# Sheet1.net
KiCad netlist of a schematic drawn in Altium Designer
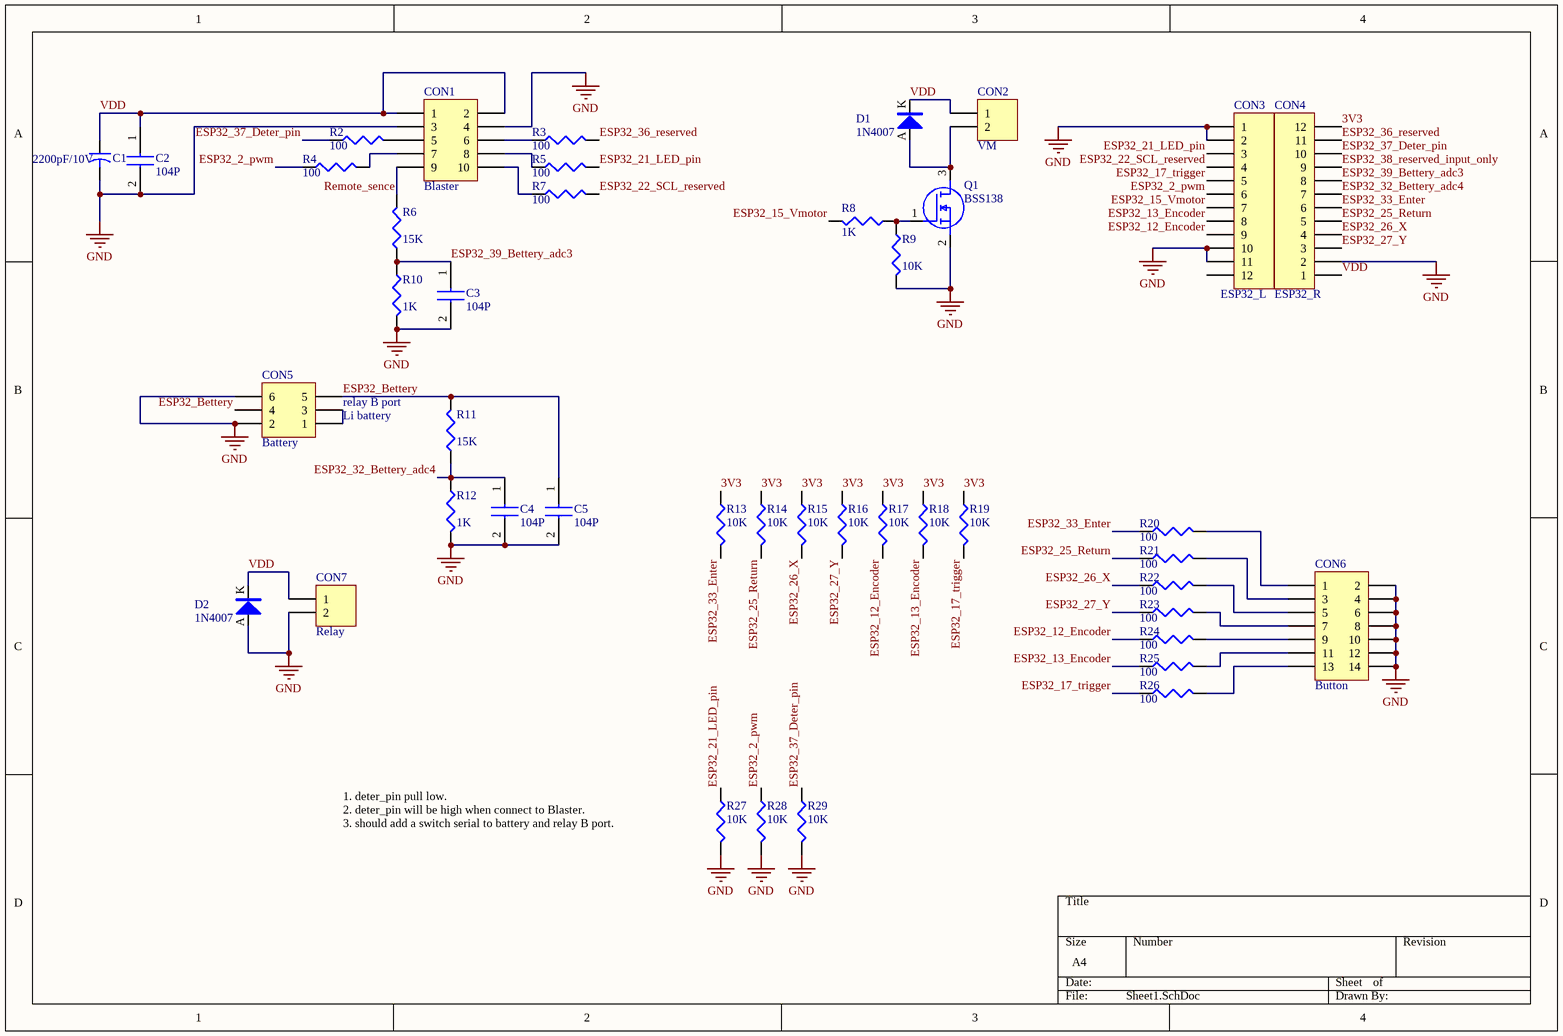
[diagram p0: Sheet1.SchDoc]

(export (version "E")
  (design (tool "Eeschema 10.0.6"))
  (components
    (comp (ref "C1")
      (value "2200pF/10V")
      (footprint "CAPR5-4X5")
      (description "Capacitor")
      (fields (field (name "Comment") "Cap2") (field (name "PUBLISHER") "Altium Limited"))
      (libsource (lib "Miscellaneous Devices") (part "Cap2"))
    )
    (comp (ref "C2")
      (value "104P")
      (footprint "SamacSys:CAPC1608X90N")
      (description "Capacitor")
      (fields
        (field (name "MANUFACTURER_PART_NUMBER") "CC0603KRX7R7BB103")
        (field (name "MOUSER PART NUMBER") "603-CC603KRX7R7BB103")
      )
      (libsource (lib "*") (part "CC0603KRX7R7BB103"))
    )
    (comp (ref "C3")
      (value "104P")
      (footprint "SamacSys:CAPC1608X90N")
      (description "Capacitor")
      (fields
        (field (name "MANUFACTURER_PART_NUMBER") "CC0603KRX7R7BB103")
        (field (name "MOUSER PART NUMBER") "603-CC603KRX7R7BB103")
      )
      (libsource (lib "*") (part "CC0603KRX7R7BB103"))
    )
    (comp (ref "C4")
      (value "104P")
      (footprint "SamacSys:CAPC1608X90N")
      (description "Capacitor")
      (fields
        (field (name "MANUFACTURER_PART_NUMBER") "CC0603KRX7R7BB103")
        (field (name "MOUSER PART NUMBER") "603-CC603KRX7R7BB103")
      )
      (libsource (lib "*") (part "CC0603KRX7R7BB103"))
    )
    (comp (ref "C5")
      (value "104P")
      (footprint "SamacSys:CAPC1608X90N")
      (description "Capacitor")
      (fields
        (field (name "MANUFACTURER_PART_NUMBER") "CC0603KRX7R7BB103")
        (field (name "MOUSER PART NUMBER") "603-CC603KRX7R7BB103")
      )
      (libsource (lib "*") (part "CC0603KRX7R7BB103"))
    )
    (comp (ref "CON1")
      (value "Blaster")
      (footprint "HDR2X5")
      (description "Header, 5-Pin, Dual row")
      (fields (field (name "PUBLISHER") "Altium Limited"))
      (libsource (lib "Miscellaneous Connectors") (part "Header 5X2"))
    )
    (comp (ref "CON2")
      (value "VM")
      (footprint "HDR1X2")
      (description "Header, 2-Pin")
      (fields (field (name "PUBLISHER") "Altium Limited"))
      (libsource (lib "Miscellaneous Connectors") (part "Header 2"))
    )
    (comp (ref "CON3")
      (value "ESP32_L")
      (footprint "HDR1X12")
      (description "Header, 12-Pin")
      (fields (field (name "PUBLISHER") "Altium Limited"))
      (libsource (lib "") (part "Header 12_1"))
    )
    (comp (ref "CON4")
      (value "ESP32_R")
      (footprint "HDR1X12")
      (description "Header, 12-Pin")
      (fields (field (name "PUBLISHER") "Altium Limited"))
      (libsource (lib "Miscellaneous Connectors") (part "Header 12"))
    )
    (comp (ref "CON5")
      (value "Battery")
      (footprint "HDR2X3")
      (description "Header, 3-Pin, Dual row")
      (fields (field (name "PUBLISHER") "Altium Limited"))
      (libsource (lib "Miscellaneous Connectors") (part "Header 3X2"))
    )
    (comp (ref "CON6")
      (value "Button")
      (footprint "HDR2X7")
      (description "Header, 7-Pin, Dual row")
      (fields (field (name "PUBLISHER") "Altium Limited"))
      (libsource (lib "Miscellaneous Connectors") (part "Header 7X2"))
    )
    (comp (ref "CON7")
      (value "Relay")
      (footprint "HDR1X2")
      (description "Header, 2-Pin")
      (fields (field (name "PUBLISHER") "Altium Limited"))
      (libsource (lib "Miscellaneous Connectors") (part "Header 2"))
    )
    (comp (ref "D1") (value "1N4007") (footprint "D3216") (libsource (lib "Diode") (part "SMD-D")))
    (comp (ref "D2") (value "1N4007") (footprint "D3216") (libsource (lib "Diode") (part "SMD-D")))
    (comp (ref "Q1")
      (value "BSS138")
      (footprint "SamacSys:SOT95P240X120-3N")
      (description "MOSFET (N-Channel)")
      (fields (field (name "MOUSER PART NUMBER") "512-BSS138"))
      (libsource (lib "*") (part "BSS138"))
    )
    (comp (ref "R2")
      (value "100")
      (footprint "J1-0603")
      (description "Resistor")
      (fields (field (name "Comment") "Res3") (field (name "PUBLISHER") "Altium Limited"))
      (libsource (lib "Miscellaneous Devices") (part "Res3"))
    )
    (comp (ref "R3")
      (value "100")
      (footprint "J1-0603")
      (description "Resistor")
      (fields (field (name "Comment") "Res3") (field (name "PUBLISHER") "Altium Limited"))
      (libsource (lib "Miscellaneous Devices") (part "Res3"))
    )
    (comp (ref "R4")
      (value "100")
      (footprint "J1-0603")
      (description "Resistor")
      (fields (field (name "Comment") "Res3") (field (name "PUBLISHER") "Altium Limited"))
      (libsource (lib "Miscellaneous Devices") (part "Res3"))
    )
    (comp (ref "R5")
      (value "100")
      (footprint "J1-0603")
      (description "Resistor")
      (fields (field (name "Comment") "Res3") (field (name "PUBLISHER") "Altium Limited"))
      (libsource (lib "Miscellaneous Devices") (part "Res3"))
    )
    (comp (ref "R6")
      (value "15K")
      (footprint "J1-0603")
      (description "Resistor")
      (fields (field (name "Comment") "Res3") (field (name "PUBLISHER") "Altium Limited"))
      (libsource (lib "Miscellaneous Devices") (part "Res3"))
    )
    (comp (ref "R7")
      (value "100")
      (footprint "J1-0603")
      (description "Resistor")
      (fields (field (name "Comment") "Res3") (field (name "PUBLISHER") "Altium Limited"))
      (libsource (lib "Miscellaneous Devices") (part "Res3"))
    )
    (comp (ref "R8")
      (value "1K")
      (footprint "J1-0603")
      (description "Resistor")
      (fields (field (name "Comment") "Res3") (field (name "PUBLISHER") "Altium Limited"))
      (libsource (lib "Miscellaneous Devices") (part "Res3"))
    )
    (comp (ref "R9")
      (value "10K")
      (footprint "J1-0603")
      (description "Resistor")
      (fields (field (name "Comment") "Res3") (field (name "PUBLISHER") "Altium Limited"))
      (libsource (lib "Miscellaneous Devices") (part "Res3"))
    )
    (comp (ref "R10")
      (value "1K")
      (footprint "J1-0603")
      (description "Resistor")
      (fields (field (name "Comment") "Res3") (field (name "PUBLISHER") "Altium Limited"))
      (libsource (lib "Miscellaneous Devices") (part "Res3"))
    )
    (comp (ref "R11")
      (value "15K")
      (footprint "J1-0603")
      (description "Resistor")
      (fields (field (name "Comment") "Res3") (field (name "PUBLISHER") "Altium Limited"))
      (libsource (lib "Miscellaneous Devices") (part "Res3"))
    )
    (comp (ref "R12")
      (value "1K")
      (footprint "J1-0603")
      (description "Resistor")
      (fields (field (name "Comment") "Res3") (field (name "PUBLISHER") "Altium Limited"))
      (libsource (lib "Miscellaneous Devices") (part "Res3"))
    )
    (comp (ref "R13")
      (value "10K")
      (footprint "J1-0603")
      (description "Resistor")
      (fields (field (name "Comment") "Res3") (field (name "PUBLISHER") "Altium Limited"))
      (libsource (lib "Miscellaneous Devices") (part "Res3"))
    )
    (comp (ref "R14")
      (value "10K")
      (footprint "J1-0603")
      (description "Resistor")
      (fields (field (name "Comment") "Res3") (field (name "PUBLISHER") "Altium Limited"))
      (libsource (lib "Miscellaneous Devices") (part "Res3"))
    )
    (comp (ref "R15")
      (value "10K")
      (footprint "J1-0603")
      (description "Resistor")
      (fields (field (name "Comment") "Res3") (field (name "PUBLISHER") "Altium Limited"))
      (libsource (lib "Miscellaneous Devices") (part "Res3"))
    )
    (comp (ref "R16")
      (value "10K")
      (footprint "J1-0603")
      (description "Resistor")
      (fields (field (name "Comment") "Res3") (field (name "PUBLISHER") "Altium Limited"))
      (libsource (lib "Miscellaneous Devices") (part "Res3"))
    )
    (comp (ref "R17")
      (value "10K")
      (footprint "J1-0603")
      (description "Resistor")
      (fields (field (name "Comment") "Res3") (field (name "PUBLISHER") "Altium Limited"))
      (libsource (lib "Miscellaneous Devices") (part "Res3"))
    )
    (comp (ref "R18")
      (value "10K")
      (footprint "J1-0603")
      (description "Resistor")
      (fields (field (name "Comment") "Res3") (field (name "PUBLISHER") "Altium Limited"))
      (libsource (lib "Miscellaneous Devices") (part "Res3"))
    )
    (comp (ref "R19")
      (value "10K")
      (footprint "J1-0603")
      (description "Resistor")
      (fields (field (name "Comment") "Res3") (field (name "PUBLISHER") "Altium Limited"))
      (libsource (lib "Miscellaneous Devices") (part "Res3"))
    )
    (comp (ref "R20")
      (value "100")
      (footprint "J1-0603")
      (description "Resistor")
      (fields (field (name "Comment") "Res3") (field (name "PUBLISHER") "Altium Limited"))
      (libsource (lib "Miscellaneous Devices") (part "Res3"))
    )
    (comp (ref "R21")
      (value "100")
      (footprint "J1-0603")
      (description "Resistor")
      (fields (field (name "Comment") "Res3") (field (name "PUBLISHER") "Altium Limited"))
      (libsource (lib "Miscellaneous Devices") (part "Res3"))
    )
    (comp (ref "R22")
      (value "100")
      (footprint "J1-0603")
      (description "Resistor")
      (fields (field (name "Comment") "Res3") (field (name "PUBLISHER") "Altium Limited"))
      (libsource (lib "Miscellaneous Devices") (part "Res3"))
    )
    (comp (ref "R23")
      (value "100")
      (footprint "J1-0603")
      (description "Resistor")
      (fields (field (name "Comment") "Res3") (field (name "PUBLISHER") "Altium Limited"))
      (libsource (lib "Miscellaneous Devices") (part "Res3"))
    )
    (comp (ref "R24")
      (value "100")
      (footprint "J1-0603")
      (description "Resistor")
      (fields (field (name "Comment") "Res3") (field (name "PUBLISHER") "Altium Limited"))
      (libsource (lib "Miscellaneous Devices") (part "Res3"))
    )
    (comp (ref "R25")
      (value "100")
      (footprint "J1-0603")
      (description "Resistor")
      (fields (field (name "Comment") "Res3") (field (name "PUBLISHER") "Altium Limited"))
      (libsource (lib "Miscellaneous Devices") (part "Res3"))
    )
    (comp (ref "R26")
      (value "100")
      (footprint "J1-0603")
      (description "Resistor")
      (fields (field (name "Comment") "Res3") (field (name "PUBLISHER") "Altium Limited"))
      (libsource (lib "Miscellaneous Devices") (part "Res3"))
    )
    (comp (ref "R27")
      (value "10K")
      (footprint "J1-0603")
      (description "Resistor")
      (fields (field (name "Comment") "Res3") (field (name "PUBLISHER") "Altium Limited"))
      (libsource (lib "Miscellaneous Devices") (part "Res3"))
    )
    (comp (ref "R28")
      (value "10K")
      (footprint "J1-0603")
      (description "Resistor")
      (fields (field (name "Comment") "Res3") (field (name "PUBLISHER") "Altium Limited"))
      (libsource (lib "Miscellaneous Devices") (part "Res3"))
    )
    (comp (ref "R29")
      (value "10K")
      (footprint "J1-0603")
      (description "Resistor")
      (fields (field (name "Comment") "Res3") (field (name "PUBLISHER") "Altium Limited"))
      (libsource (lib "Miscellaneous Devices") (part "Res3"))
    )
  )
  (nets
    (net (code "1") (name "/3V3") (class "Default")
      (node (ref "CON4") (pin "12") (pinfunction "12_12") (pintype "passive"))
      (node (ref "R13") (pin "1") (pinfunction "1_1") (pintype "passive"))
      (node (ref "R14") (pin "1") (pinfunction "1_1") (pintype "passive"))
      (node (ref "R15") (pin "1") (pinfunction "1_1") (pintype "passive"))
      (node (ref "R16") (pin "1") (pinfunction "1_1") (pintype "passive"))
      (node (ref "R17") (pin "1") (pinfunction "1_1") (pintype "passive"))
      (node (ref "R18") (pin "1") (pinfunction "1_1") (pintype "passive"))
      (node (ref "R19") (pin "1") (pinfunction "1_1") (pintype "passive"))
    )
    (net (code "2") (name "/ESP32_2_pwm") (class "Default")
      (node (ref "CON3") (pin "6") (pinfunction "6_6") (pintype "passive"))
      (node (ref "R28") (pin "1") (pinfunction "1_1") (pintype "passive"))
      (node (ref "R4") (pin "1") (pinfunction "1_1") (pintype "passive"))
    )
    (net (code "3") (name "/ESP32_12_Encoder") (class "Default")
      (node (ref "CON3") (pin "9") (pinfunction "9_9") (pintype "passive"))
      (node (ref "R17") (pin "2") (pinfunction "2_2") (pintype "passive"))
      (node (ref "R24") (pin "1") (pinfunction "1_1") (pintype "passive"))
    )
    (net (code "4") (name "/ESP32_13_Encoder") (class "Default")
      (node (ref "CON3") (pin "8") (pinfunction "8_8") (pintype "passive"))
      (node (ref "R18") (pin "2") (pinfunction "2_2") (pintype "passive"))
      (node (ref "R25") (pin "1") (pinfunction "1_1") (pintype "passive"))
    )
    (net (code "5") (name "/ESP32_15_Vmotor") (class "Default")
      (node (ref "CON3") (pin "7") (pinfunction "7_7") (pintype "passive"))
      (node (ref "R8") (pin "2") (pinfunction "2_2") (pintype "passive"))
    )
    (net (code "6") (name "/ESP32_17_trigger") (class "Default")
      (node (ref "CON3") (pin "5") (pinfunction "5_5") (pintype "passive"))
      (node (ref "R19") (pin "2") (pinfunction "2_2") (pintype "passive"))
      (node (ref "R26") (pin "1") (pinfunction "1_1") (pintype "passive"))
    )
    (net (code "7") (name "/ESP32_21_LED_pin") (class "Default")
      (node (ref "CON3") (pin "3") (pinfunction "3_3") (pintype "passive"))
      (node (ref "R27") (pin "1") (pinfunction "1_1") (pintype "passive"))
      (node (ref "R5") (pin "2") (pinfunction "2_2") (pintype "passive"))
    )
    (net (code "8") (name "/ESP32_22_SCL_reserved") (class "Default")
      (node (ref "CON3") (pin "4") (pinfunction "4_4") (pintype "passive"))
      (node (ref "R7") (pin "2") (pinfunction "2_2") (pintype "passive"))
    )
    (net (code "9") (name "/ESP32_25_Return") (class "Default")
      (node (ref "CON4") (pin "5") (pinfunction "5_5") (pintype "passive"))
      (node (ref "R14") (pin "2") (pinfunction "2_2") (pintype "passive"))
      (node (ref "R21") (pin "1") (pinfunction "1_1") (pintype "passive"))
    )
    (net (code "10") (name "/ESP32_26_X") (class "Default")
      (node (ref "CON4") (pin "4") (pinfunction "4_4") (pintype "passive"))
      (node (ref "R15") (pin "2") (pinfunction "2_2") (pintype "passive"))
      (node (ref "R22") (pin "1") (pinfunction "1_1") (pintype "passive"))
    )
    (net (code "11") (name "/ESP32_27_Y") (class "Default")
      (node (ref "CON4") (pin "3") (pinfunction "3_3") (pintype "passive"))
      (node (ref "R16") (pin "2") (pinfunction "2_2") (pintype "passive"))
      (node (ref "R23") (pin "1") (pinfunction "1_1") (pintype "passive"))
    )
    (net (code "12") (name "/ESP32_32_Bettery_adc4") (class "Default")
      (node (ref "C4") (pin "1") (pinfunction "1_1") (pintype "passive"))
      (node (ref "CON4") (pin "7") (pinfunction "7_7") (pintype "passive"))
      (node (ref "R11") (pin "1") (pinfunction "1_1") (pintype "passive"))
      (node (ref "R12") (pin "1") (pinfunction "1_1") (pintype "passive"))
    )
    (net (code "13") (name "/ESP32_33_Enter") (class "Default")
      (node (ref "CON4") (pin "6") (pinfunction "6_6") (pintype "passive"))
      (node (ref "R13") (pin "2") (pinfunction "2_2") (pintype "passive"))
      (node (ref "R20") (pin "1") (pinfunction "1_1") (pintype "passive"))
    )
    (net (code "14") (name "/ESP32_36_reserved") (class "Default")
      (node (ref "CON4") (pin "11") (pinfunction "11_11") (pintype "passive"))
      (node (ref "R3") (pin "2") (pinfunction "2_2") (pintype "passive"))
    )
    (net (code "15") (name "/ESP32_37_Deter_pin") (class "Default")
      (node (ref "CON4") (pin "10") (pinfunction "10_10") (pintype "passive"))
      (node (ref "R2") (pin "1") (pinfunction "1_1") (pintype "passive"))
      (node (ref "R29") (pin "1") (pinfunction "1_1") (pintype "passive"))
    )
    (net (code "16") (name "/ESP32_38_reserved_input_only") (class "Default")
      (node (ref "CON4") (pin "9") (pinfunction "9_9") (pintype "passive"))
    )
    (net (code "17") (name "/ESP32_39_Bettery_adc3") (class "Default")
      (node (ref "C3") (pin "1") (pinfunction "1_1") (pintype "passive"))
      (node (ref "CON4") (pin "8") (pinfunction "8_8") (pintype "passive"))
      (node (ref "R10") (pin "1") (pinfunction "1_1") (pintype "passive"))
      (node (ref "R6") (pin "1") (pinfunction "1_1") (pintype "passive"))
    )
    (net (code "18") (name "/ESP32_Bettery") (class "Default")
      (node (ref "C5") (pin "1") (pinfunction "1_1") (pintype "passive"))
      (node (ref "CON5") (pin "4") (pinfunction "4_4") (pintype "passive"))
      (node (ref "CON5") (pin "5") (pinfunction "5_5") (pintype "passive"))
      (node (ref "R11") (pin "2") (pinfunction "2_2") (pintype "passive"))
    )
    (net (code "19") (name "/Remote_sence") (class "Default")
      (node (ref "CON1") (pin "9") (pinfunction "9_9") (pintype "passive"))
      (node (ref "R6") (pin "2") (pinfunction "2_2") (pintype "passive"))
    )
    (net (code "20") (name "/VDD") (class "Default")
      (node (ref "C1") (pin "1") (pinfunction "1_1") (pintype "passive"))
      (node (ref "C2") (pin "1") (pinfunction "1_1") (pintype "passive"))
      (node (ref "CON1") (pin "1") (pinfunction "1_1") (pintype "passive"))
      (node (ref "CON1") (pin "2") (pinfunction "2_2") (pintype "passive"))
      (node (ref "CON2") (pin "1") (pinfunction "1_1") (pintype "passive"))
      (node (ref "CON4") (pin "1") (pinfunction "1_1") (pintype "passive"))
      (node (ref "CON7") (pin "1") (pinfunction "1_1") (pintype "passive"))
      (node (ref "D1") (pin "K") (pinfunction "K_K") (pintype "passive"))
      (node (ref "D2") (pin "K") (pinfunction "K_K") (pintype "passive"))
    )
    (net (code "21") (name "GND") (class "Default")
      (node (ref "C1") (pin "2") (pinfunction "2_2") (pintype "passive"))
      (node (ref "C2") (pin "2") (pinfunction "2_2") (pintype "passive"))
      (node (ref "C3") (pin "2") (pinfunction "2_2") (pintype "passive"))
      (node (ref "C4") (pin "2") (pinfunction "2_2") (pintype "passive"))
      (node (ref "C5") (pin "2") (pinfunction "2_2") (pintype "passive"))
      (node (ref "CON1") (pin "3") (pinfunction "3_3") (pintype "passive"))
      (node (ref "CON1") (pin "4") (pinfunction "4_4") (pintype "passive"))
      (node (ref "CON3") (pin "1") (pinfunction "1_1") (pintype "passive"))
      (node (ref "CON3") (pin "10") (pinfunction "10_10") (pintype "passive"))
      (node (ref "CON3") (pin "11") (pinfunction "11_11") (pintype "passive"))
      (node (ref "CON3") (pin "2") (pinfunction "2_2") (pintype "passive"))
      (node (ref "CON4") (pin "2") (pinfunction "2_2") (pintype "passive"))
      (node (ref "CON5") (pin "2") (pinfunction "2_2") (pintype "passive"))
      (node (ref "CON5") (pin "6") (pinfunction "6_6") (pintype "passive"))
      (node (ref "CON6") (pin "10") (pinfunction "10_10") (pintype "passive"))
      (node (ref "CON6") (pin "12") (pinfunction "12_12") (pintype "passive"))
      (node (ref "CON6") (pin "14") (pinfunction "14_14") (pintype "passive"))
      (node (ref "CON6") (pin "2") (pinfunction "2_2") (pintype "passive"))
      (node (ref "CON6") (pin "4") (pinfunction "4_4") (pintype "passive"))
      (node (ref "CON6") (pin "6") (pinfunction "6_6") (pintype "passive"))
      (node (ref "CON6") (pin "8") (pinfunction "8_8") (pintype "passive"))
      (node (ref "CON7") (pin "2") (pinfunction "2_2") (pintype "passive"))
      (node (ref "D2") (pin "A") (pinfunction "A_A") (pintype "passive"))
      (node (ref "Q1") (pin "2") (pinfunction "S_2") (pintype "passive"))
      (node (ref "R10") (pin "2") (pinfunction "2_2") (pintype "passive"))
      (node (ref "R12") (pin "2") (pinfunction "2_2") (pintype "passive"))
      (node (ref "R27") (pin "2") (pinfunction "2_2") (pintype "passive"))
      (node (ref "R28") (pin "2") (pinfunction "2_2") (pintype "passive"))
      (node (ref "R29") (pin "2") (pinfunction "2_2") (pintype "passive"))
      (node (ref "R9") (pin "2") (pinfunction "2_2") (pintype "passive"))
    )
    (net (code "22") (name "Net-(CON1-Pad5)") (class "Default")
      (node (ref "CON1") (pin "5") (pinfunction "5_5") (pintype "passive"))
      (node (ref "R2") (pin "2") (pinfunction "2_2") (pintype "passive"))
    )
    (net (code "23") (name "Net-(CON1-Pad6)") (class "Default")
      (node (ref "CON1") (pin "6") (pinfunction "6_6") (pintype "passive"))
      (node (ref "R3") (pin "1") (pinfunction "1_1") (pintype "passive"))
    )
    (net (code "24") (name "Net-(CON1-Pad7)") (class "Default")
      (node (ref "CON1") (pin "7") (pinfunction "7_7") (pintype "passive"))
      (node (ref "R4") (pin "2") (pinfunction "2_2") (pintype "passive"))
    )
    (net (code "25") (name "Net-(CON1-Pad8)") (class "Default")
      (node (ref "CON1") (pin "8") (pinfunction "8_8") (pintype "passive"))
      (node (ref "R5") (pin "1") (pinfunction "1_1") (pintype "passive"))
    )
    (net (code "26") (name "Net-(CON1-Pad10)") (class "Default")
      (node (ref "CON1") (pin "10") (pinfunction "10_10") (pintype "passive"))
      (node (ref "R7") (pin "1") (pinfunction "1_1") (pintype "passive"))
    )
    (net (code "27") (name "Net-(CON5-Pad1)") (class "Default")
      (node (ref "CON5") (pin "1") (pinfunction "1_1") (pintype "passive"))
      (node (ref "CON5") (pin "3") (pinfunction "3_3") (pintype "passive"))
    )
    (net (code "28") (name "Net-(CON6-Pad1)") (class "Default")
      (node (ref "CON6") (pin "1") (pinfunction "1_1") (pintype "passive"))
      (node (ref "R20") (pin "2") (pinfunction "2_2") (pintype "passive"))
    )
    (net (code "29") (name "Net-(CON6-Pad3)") (class "Default")
      (node (ref "CON6") (pin "3") (pinfunction "3_3") (pintype "passive"))
      (node (ref "R21") (pin "2") (pinfunction "2_2") (pintype "passive"))
    )
    (net (code "30") (name "Net-(CON6-Pad5)") (class "Default")
      (node (ref "CON6") (pin "5") (pinfunction "5_5") (pintype "passive"))
      (node (ref "R22") (pin "2") (pinfunction "2_2") (pintype "passive"))
    )
    (net (code "31") (name "Net-(CON6-Pad7)") (class "Default")
      (node (ref "CON6") (pin "7") (pinfunction "7_7") (pintype "passive"))
      (node (ref "R23") (pin "2") (pinfunction "2_2") (pintype "passive"))
    )
    (net (code "32") (name "Net-(CON6-Pad9)") (class "Default")
      (node (ref "CON6") (pin "9") (pinfunction "9_9") (pintype "passive"))
      (node (ref "R24") (pin "2") (pinfunction "2_2") (pintype "passive"))
    )
    (net (code "33") (name "Net-(CON6-Pad11)") (class "Default")
      (node (ref "CON6") (pin "11") (pinfunction "11_11") (pintype "passive"))
      (node (ref "R25") (pin "2") (pinfunction "2_2") (pintype "passive"))
    )
    (net (code "34") (name "Net-(CON6-Pad13)") (class "Default")
      (node (ref "CON6") (pin "13") (pinfunction "13_13") (pintype "passive"))
      (node (ref "R26") (pin "2") (pinfunction "2_2") (pintype "passive"))
    )
    (net (code "35") (name "Net-(Q1-D)") (class "Default")
      (node (ref "CON2") (pin "2") (pinfunction "2_2") (pintype "passive"))
      (node (ref "D1") (pin "A") (pinfunction "A_A") (pintype "passive"))
      (node (ref "Q1") (pin "3") (pinfunction "D_3") (pintype "passive"))
    )
    (net (code "36") (name "Net-(Q1-G)") (class "Default")
      (node (ref "Q1") (pin "1") (pinfunction "G_1") (pintype "passive"))
      (node (ref "R8") (pin "1") (pinfunction "1_1") (pintype "passive"))
      (node (ref "R9") (pin "1") (pinfunction "1_1") (pintype "passive"))
    )
    (net (code "37") (name "unconnected-(CON3-Pad12)") (class "Default")
      (node (ref "CON3") (pin "12") (pinfunction "12_12") (pintype "passive"))
    )
  )
)
